# ATMEGA328PB_EVAL.net
KiCad netlist of a schematic drawn in EAGLE
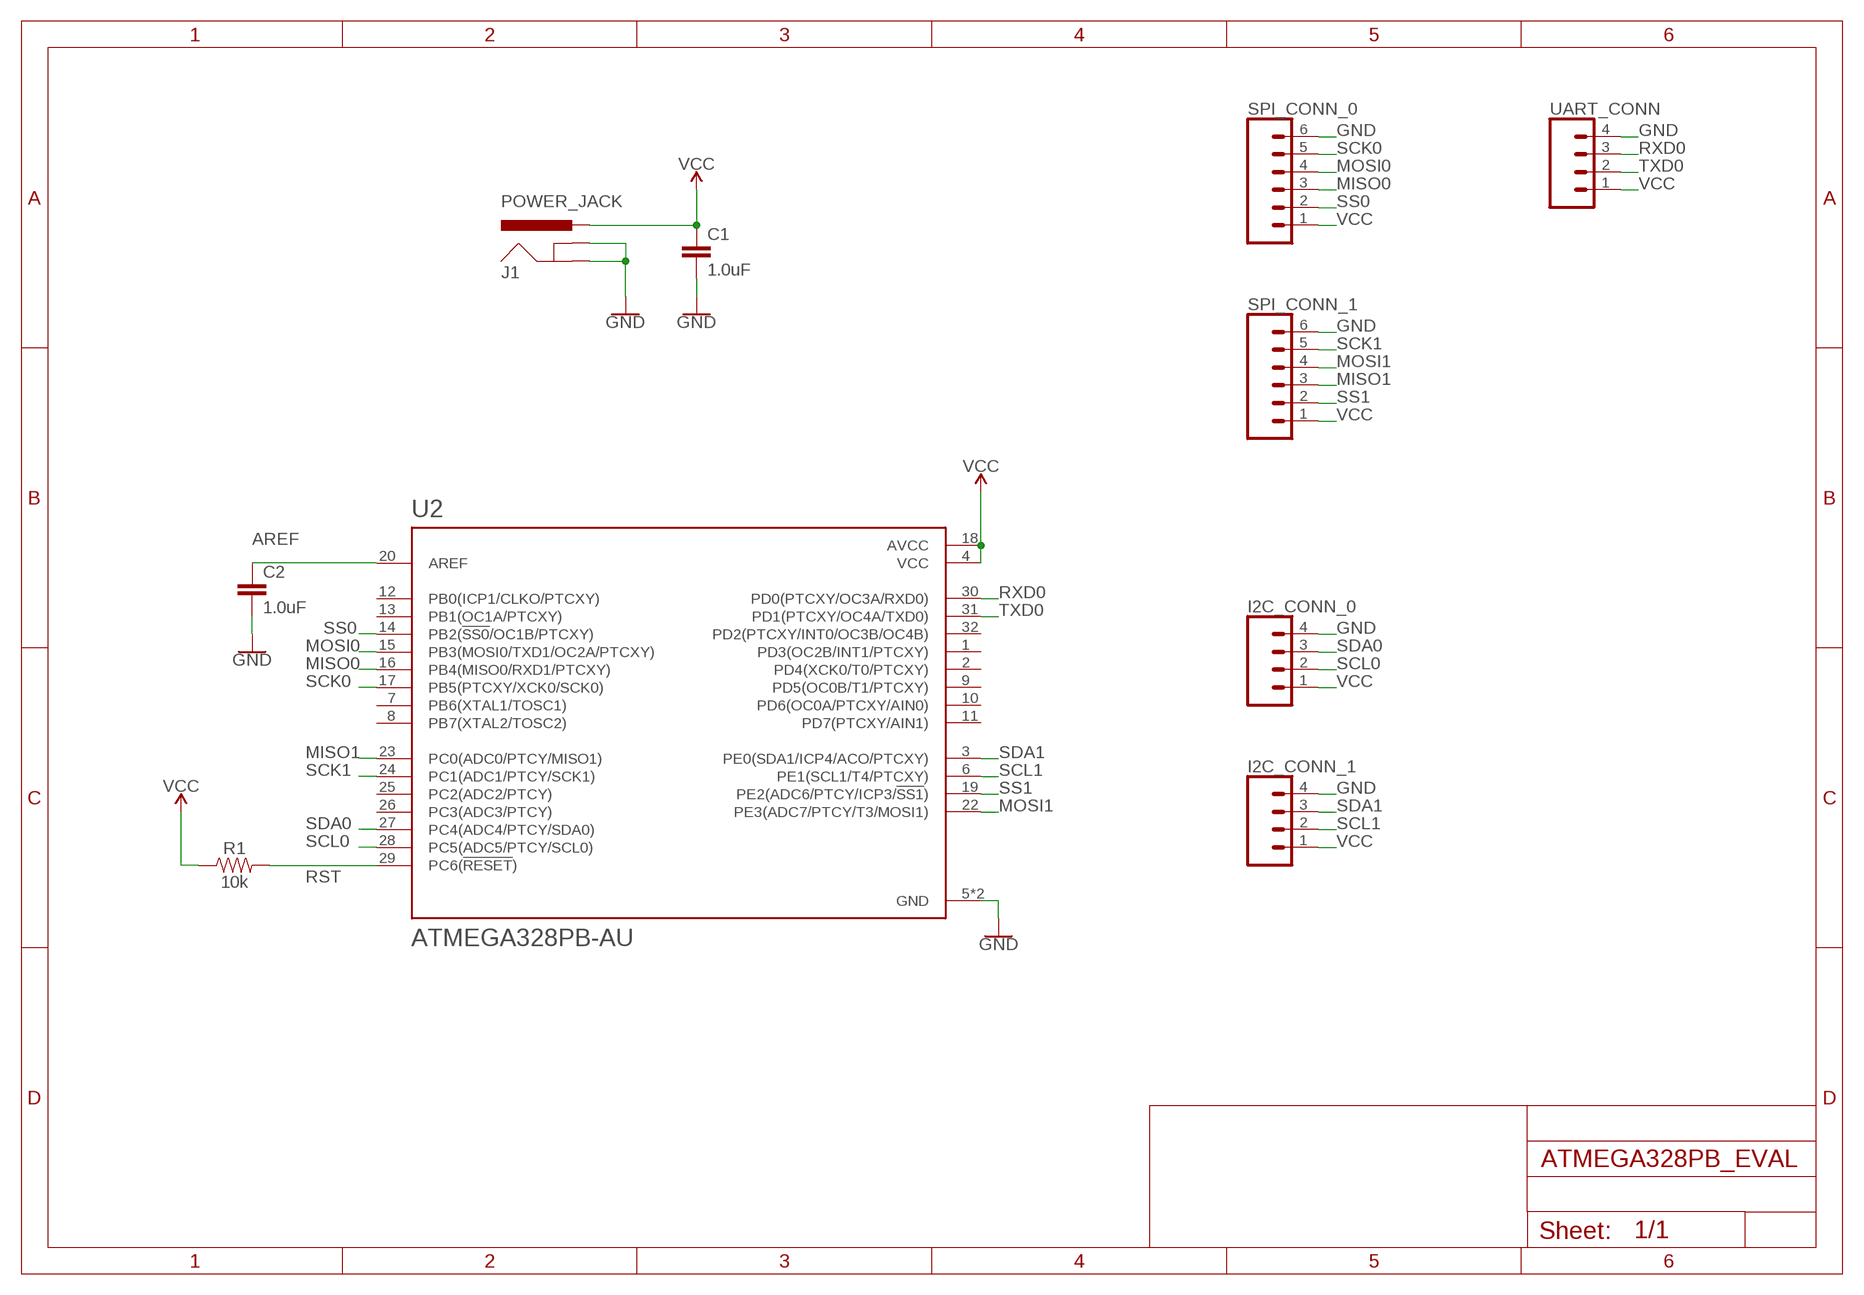
[diagram p0: schematic, sheet 1]

(export (version "E")
  (design (tool "Eeschema 10.0.6"))
  (components
    (comp (ref "C1")
      (value "1.0uF")
      (footprint "eagle-import:0603")
      (libsource (lib "eagle-import") (part "1.0UF-0603-16V-10%"))
    )
    (comp (ref "C2")
      (value "1.0uF")
      (footprint "eagle-import:0603")
      (libsource (lib "eagle-import") (part "1.0UF-0603-16V-10%"))
    )
    (comp (ref "I2C_CONN_0")
      (value "CONN_04")
      (footprint "eagle-import:1X04")
      (libsource (lib "eagle-import") (part "CONN_04"))
    )
    (comp (ref "I2C_CONN_1")
      (value "CONN_04")
      (footprint "eagle-import:1X04")
      (libsource (lib "eagle-import") (part "CONN_04"))
    )
    (comp (ref "J1")
      (value "POWER_JACK")
      (footprint "eagle-import:POWER_JACK_PTH")
      (libsource (lib "eagle-import") (part "POWER_JACK"))
    )
    (comp (ref "R1")
      (value "10k")
      (footprint "eagle-import:0603")
      (libsource (lib "eagle-import") (part "10KOHM-0603-1/10W-1%"))
    )
    (comp (ref "SPI_CONN_0")
      (value "CONN_06SILK_FEMALE_PTH")
      (footprint "eagle-import:1X06")
      (libsource (lib "eagle-import") (part "CONN_06SILK_FEMALE_PTH"))
    )
    (comp (ref "SPI_CONN_1")
      (value "CONN_06SILK_FEMALE_PTH")
      (footprint "eagle-import:1X06")
      (libsource (lib "eagle-import") (part "CONN_06SILK_FEMALE_PTH"))
    )
    (comp (ref "U2")
      (value "ATMEGA328PB-AU")
      (footprint "eagle-import:QFP80P900X900X120-32N")
      (fields (field (name "MF") "Microchip Technology / Atmel"))
      (libsource (lib "eagle-import") (part "ATMEGA328PB-AU"))
    )
    (comp (ref "UART_CONN")
      (value "CONN_04")
      (footprint "eagle-import:1X04")
      (libsource (lib "eagle-import") (part "CONN_04"))
    )
  )
  (nets
    (net (code "1") (name "/AREF") (class "Default")
      (node (ref "C2") (pin "1") (pinfunction "1_1") (pintype "passive"))
      (node (ref "U2") (pin "20") (pinfunction "AREF_20") (pintype "input"))
    )
    (net (code "2") (name "/MISO0") (class "Default")
      (node (ref "SPI_CONN_0") (pin "3") (pinfunction "3_3") (pintype "passive"))
      (node (ref "U2") (pin "16") (pinfunction "PB4(MISO0/RXD1/PTCXY)_16") (pintype "bidirectional"))
    )
    (net (code "3") (name "/MISO1") (class "Default")
      (node (ref "SPI_CONN_1") (pin "3") (pinfunction "3_3") (pintype "passive"))
      (node (ref "U2") (pin "23") (pinfunction "PC0(ADC0/PTCY/MISO1)_23") (pintype "bidirectional"))
    )
    (net (code "4") (name "/MOSI0") (class "Default")
      (node (ref "SPI_CONN_0") (pin "4") (pinfunction "4_4") (pintype "passive"))
      (node (ref "U2") (pin "15") (pinfunction "PB3(MOSI0/TXD1/OC2A/PTCXY)_15") (pintype "bidirectional"))
    )
    (net (code "5") (name "/MOSI1") (class "Default")
      (node (ref "SPI_CONN_1") (pin "4") (pinfunction "4_4") (pintype "passive"))
      (node (ref "U2") (pin "22") (pinfunction "PE3(ADC7/PTCY/T3/MOSI1)_22") (pintype "bidirectional"))
    )
    (net (code "6") (name "/RST") (class "Default")
      (node (ref "R1") (pin "2") (pinfunction "2_2") (pintype "passive"))
      (node (ref "U2") (pin "29") (pinfunction "PC6(~{RESET})_29") (pintype "bidirectional"))
    )
    (net (code "7") (name "/RXD0") (class "Default")
      (node (ref "U2") (pin "30") (pinfunction "PD0(PTCXY/OC3A/RXD0)_30") (pintype "bidirectional"))
      (node (ref "UART_CONN") (pin "3") (pinfunction "3_3") (pintype "passive"))
    )
    (net (code "8") (name "/SCK0") (class "Default")
      (node (ref "SPI_CONN_0") (pin "5") (pinfunction "5_5") (pintype "passive"))
      (node (ref "U2") (pin "17") (pinfunction "PB5(PTCXY/XCK0/SCK0)_17") (pintype "bidirectional"))
    )
    (net (code "9") (name "/SCK1") (class "Default")
      (node (ref "SPI_CONN_1") (pin "5") (pinfunction "5_5") (pintype "passive"))
      (node (ref "U2") (pin "24") (pinfunction "PC1(ADC1/PTCY/SCK1)_24") (pintype "bidirectional"))
    )
    (net (code "10") (name "/SCL0") (class "Default")
      (node (ref "I2C_CONN_0") (pin "2") (pinfunction "2_2") (pintype "passive"))
      (node (ref "U2") (pin "28") (pinfunction "PC5(ADC5/PTCY/SCL0)_28") (pintype "bidirectional"))
    )
    (net (code "11") (name "/SCL1") (class "Default")
      (node (ref "I2C_CONN_1") (pin "2") (pinfunction "2_2") (pintype "passive"))
      (node (ref "U2") (pin "6") (pinfunction "PE1(SCL1/T4/PTCXY)_6") (pintype "bidirectional"))
    )
    (net (code "12") (name "/SDA0") (class "Default")
      (node (ref "I2C_CONN_0") (pin "3") (pinfunction "3_3") (pintype "passive"))
      (node (ref "U2") (pin "27") (pinfunction "PC4(ADC4/PTCY/SDA0)_27") (pintype "bidirectional"))
    )
    (net (code "13") (name "/SDA1") (class "Default")
      (node (ref "I2C_CONN_1") (pin "3") (pinfunction "3_3") (pintype "passive"))
      (node (ref "U2") (pin "3") (pinfunction "PE0(SDA1/ICP4/ACO/PTCXY)_3") (pintype "bidirectional"))
    )
    (net (code "14") (name "/SS0") (class "Default")
      (node (ref "SPI_CONN_0") (pin "2") (pinfunction "2_2") (pintype "passive"))
      (node (ref "U2") (pin "14") (pinfunction "PB2(~{SS0}/OC1B/PTCXY)_14") (pintype "bidirectional"))
    )
    (net (code "15") (name "/SS1") (class "Default")
      (node (ref "SPI_CONN_1") (pin "2") (pinfunction "2_2") (pintype "passive"))
      (node (ref "U2") (pin "19") (pinfunction "PE2(ADC6/PTCY/ICP3/~{SS1})_19") (pintype "bidirectional"))
    )
    (net (code "16") (name "/TXD0") (class "Default")
      (node (ref "U2") (pin "31") (pinfunction "PD1(PTCXY/OC4A/TXD0)_31") (pintype "bidirectional"))
      (node (ref "UART_CONN") (pin "2") (pinfunction "2_2") (pintype "passive"))
    )
    (net (code "17") (name "GND") (class "Default")
      (node (ref "C1") (pin "2") (pinfunction "2_2") (pintype "passive"))
      (node (ref "C2") (pin "2") (pinfunction "2_2") (pintype "passive"))
      (node (ref "I2C_CONN_0") (pin "4") (pinfunction "4_4") (pintype "passive"))
      (node (ref "I2C_CONN_1") (pin "4") (pinfunction "4_4") (pintype "passive"))
      (node (ref "J1") (pin "GND") (pinfunction "GND_GND") (pintype "bidirectional"))
      (node (ref "J1") (pin "GNDBREAK") (pinfunction "GNDBREAK_GNDBREAK") (pintype "bidirectional"))
      (node (ref "SPI_CONN_0") (pin "6") (pinfunction "6_6") (pintype "passive"))
      (node (ref "SPI_CONN_1") (pin "6") (pinfunction "6_6") (pintype "passive"))
      (node (ref "U2") (pin "21") (pinfunction "GND_21") (pintype "power_in"))
      (node (ref "U2") (pin "5") (pinfunction "GND_5") (pintype "power_in"))
      (node (ref "UART_CONN") (pin "4") (pinfunction "4_4") (pintype "passive"))
    )
    (net (code "18") (name "VCC") (class "Default")
      (node (ref "C1") (pin "1") (pinfunction "1_1") (pintype "passive"))
      (node (ref "I2C_CONN_0") (pin "1") (pinfunction "1_1") (pintype "passive"))
      (node (ref "I2C_CONN_1") (pin "1") (pinfunction "1_1") (pintype "passive"))
      (node (ref "J1") (pin "PWR") (pinfunction "PWR_PWR") (pintype "bidirectional"))
      (node (ref "R1") (pin "1") (pinfunction "1_1") (pintype "passive"))
      (node (ref "SPI_CONN_0") (pin "1") (pinfunction "1_1") (pintype "passive"))
      (node (ref "SPI_CONN_1") (pin "1") (pinfunction "1_1") (pintype "passive"))
      (node (ref "U2") (pin "18") (pinfunction "AVCC_18") (pintype "power_in"))
      (node (ref "U2") (pin "4") (pinfunction "VCC_4") (pintype "power_in"))
      (node (ref "UART_CONN") (pin "1") (pinfunction "1_1") (pintype "passive"))
    )
    (net (code "19") (name "unconnected-(U2-PB0(ICP1{slash}CLKO{slash}PTCXY)-Pad12)") (class "Default")
      (node (ref "U2") (pin "12") (pinfunction "PB0(ICP1/CLKO/PTCXY)_12") (pintype "bidirectional"))
    )
    (net (code "20") (name "unconnected-(U2-PB1(OC1A{slash}PTCXY)-Pad13)") (class "Default")
      (node (ref "U2") (pin "13") (pinfunction "PB1(OC1A/PTCXY)_13") (pintype "bidirectional"))
    )
    (net (code "21") (name "unconnected-(U2-PB6(XTAL1{slash}TOSC1)-Pad7)") (class "Default")
      (node (ref "U2") (pin "7") (pinfunction "PB6(XTAL1/TOSC1)_7") (pintype "bidirectional"))
    )
    (net (code "22") (name "unconnected-(U2-PB7(XTAL2{slash}TOSC2)-Pad8)") (class "Default")
      (node (ref "U2") (pin "8") (pinfunction "PB7(XTAL2/TOSC2)_8") (pintype "bidirectional"))
    )
    (net (code "23") (name "unconnected-(U2-PC2(ADC2{slash}PTCY)-Pad25)") (class "Default")
      (node (ref "U2") (pin "25") (pinfunction "PC2(ADC2/PTCY)_25") (pintype "bidirectional"))
    )
    (net (code "24") (name "unconnected-(U2-PC3(ADC3{slash}PTCY)-Pad26)") (class "Default")
      (node (ref "U2") (pin "26") (pinfunction "PC3(ADC3/PTCY)_26") (pintype "bidirectional"))
    )
    (net (code "25") (name "unconnected-(U2-PD2(PTCXY{slash}INT0{slash}OC3B{slash}OC4B)-Pad32)") (class "Default")
      (node (ref "U2") (pin "32") (pinfunction "PD2(PTCXY/INT0/OC3B/OC4B)_32") (pintype "bidirectional"))
    )
    (net (code "26") (name "unconnected-(U2-PD3(OC2B{slash}INT1{slash}PTCXY)-Pad1)") (class "Default")
      (node (ref "U2") (pin "1") (pinfunction "PD3(OC2B/INT1/PTCXY)_1") (pintype "bidirectional"))
    )
    (net (code "27") (name "unconnected-(U2-PD4(XCK0{slash}T0{slash}PTCXY)-Pad2)") (class "Default")
      (node (ref "U2") (pin "2") (pinfunction "PD4(XCK0/T0/PTCXY)_2") (pintype "bidirectional"))
    )
    (net (code "28") (name "unconnected-(U2-PD5(OC0B{slash}T1{slash}PTCXY)-Pad9)") (class "Default")
      (node (ref "U2") (pin "9") (pinfunction "PD5(OC0B/T1/PTCXY)_9") (pintype "bidirectional"))
    )
    (net (code "29") (name "unconnected-(U2-PD6(OC0A{slash}PTCXY{slash}AIN0)-Pad10)") (class "Default")
      (node (ref "U2") (pin "10") (pinfunction "PD6(OC0A/PTCXY/AIN0)_10") (pintype "bidirectional"))
    )
    (net (code "30") (name "unconnected-(U2-PD7(PTCXY{slash}AIN1)-Pad11)") (class "Default")
      (node (ref "U2") (pin "11") (pinfunction "PD7(PTCXY/AIN1)_11") (pintype "bidirectional"))
    )
  )
)
